# RF_Module.net
KiCad netlist of a schematic drawn in Altium Designer
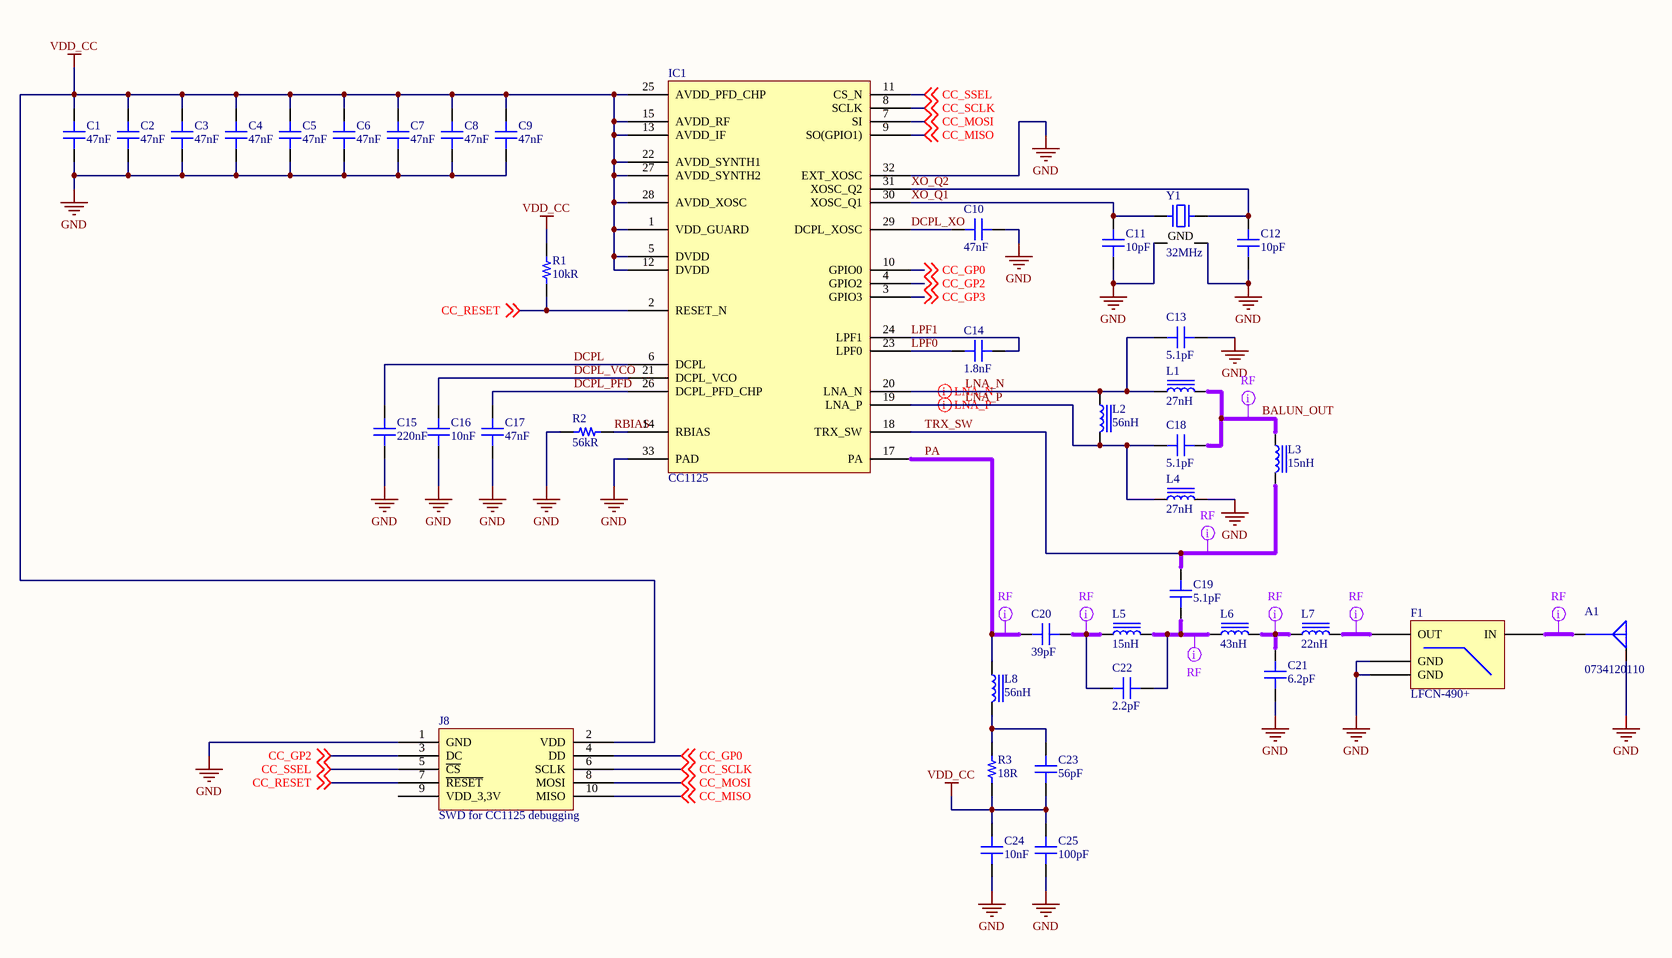
[diagram p0: RF Module.SchDoc]

(export (version "E")
  (design (tool "Eeschema 10.0.6"))
  (components
    (comp (ref "A1")
      (value "0734120110")
      (footprint "MOLEX SD-734120110")
      (description "Conn Micro Coaxial RCP 0Hz to 6GHz 50Ohm Solder ST SMD Gold Embossed T/R")
      (libsource (lib "SCH - RF - ANTENNA - BASIC ANTENNA") (part "Basic Antenna"))
    )
    (comp (ref "C1")
      (value "47nF")
      (footprint "CAP 0402/1005")
      (description "CAP CER 0.047UF 10V X7R 0402")
      (fields (field (name "TOLERANCE") "10%") (field (name "VOLTAGE") "16V"))
      (libsource (lib "SCH - PASSIVES - CAPACITOR") (part "Capacitor"))
    )
    (comp (ref "C2")
      (value "47nF")
      (footprint "CAP 0402/1005")
      (description "CAP CER 0.047UF 10V X7R 0402")
      (fields (field (name "TOLERANCE") "10%") (field (name "VOLTAGE") "16V"))
      (libsource (lib "SCH - PASSIVES - CAPACITOR") (part "Capacitor"))
    )
    (comp (ref "C3")
      (value "47nF")
      (footprint "CAP 0402/1005")
      (description "CAP CER 0.047UF 10V X7R 0402")
      (fields (field (name "TOLERANCE") "10%") (field (name "VOLTAGE") "16V"))
      (libsource (lib "SCH - PASSIVES - CAPACITOR") (part "Capacitor"))
    )
    (comp (ref "C4")
      (value "47nF")
      (footprint "CAP 0402/1005")
      (description "CAP CER 0.047UF 10V X7R 0402")
      (fields (field (name "TOLERANCE") "10%") (field (name "VOLTAGE") "16V"))
      (libsource (lib "SCH - PASSIVES - CAPACITOR") (part "Capacitor"))
    )
    (comp (ref "C5")
      (value "47nF")
      (footprint "CAP 0402/1005")
      (description "CAP CER 0.047UF 10V X7R 0402")
      (fields (field (name "TOLERANCE") "10%") (field (name "VOLTAGE") "16V"))
      (libsource (lib "SCH - PASSIVES - CAPACITOR") (part "Capacitor"))
    )
    (comp (ref "C6")
      (value "47nF")
      (footprint "CAP 0402/1005")
      (description "CAP CER 0.047UF 10V X7R 0402")
      (fields (field (name "TOLERANCE") "10%") (field (name "VOLTAGE") "16V"))
      (libsource (lib "SCH - PASSIVES - CAPACITOR") (part "Capacitor"))
    )
    (comp (ref "C7")
      (value "47nF")
      (footprint "CAP 0402/1005")
      (description "CAP CER 0.047UF 10V X7R 0402")
      (fields (field (name "TOLERANCE") "10%") (field (name "VOLTAGE") "16V"))
      (libsource (lib "SCH - PASSIVES - CAPACITOR") (part "Capacitor"))
    )
    (comp (ref "C8")
      (value "47nF")
      (footprint "CAP 0402/1005")
      (description "CAP CER 0.047UF 10V X7R 0402")
      (fields (field (name "TOLERANCE") "10%") (field (name "VOLTAGE") "16V"))
      (libsource (lib "SCH - PASSIVES - CAPACITOR") (part "Capacitor"))
    )
    (comp (ref "C9")
      (value "47nF")
      (footprint "CAP 0402/1005")
      (description "CAP CER 0.047UF 10V X7R 0402")
      (fields (field (name "TOLERANCE") "10%") (field (name "VOLTAGE") "16V"))
      (libsource (lib "SCH - PASSIVES - CAPACITOR") (part "Capacitor"))
    )
    (comp (ref "C10")
      (value "47nF")
      (footprint "CAP 0402/1005")
      (description "CAP CER 0.047UF 10V X7R 0402")
      (fields (field (name "TOLERANCE") "10%") (field (name "VOLTAGE") "16V"))
      (libsource (lib "SCH - PASSIVES - CAPACITOR") (part "Capacitor"))
    )
    (comp (ref "C11")
      (value "10pF")
      (footprint "CAP 0402/1005")
      (description "CAP CER 10PF 50V C0G/NPO 0402")
      (fields (field (name "TOLERANCE") "5%") (field (name "VOLTAGE") "50V"))
      (libsource (lib "SCH - PASSIVES - CAPACITOR") (part "Capacitor"))
    )
    (comp (ref "C12")
      (value "10pF")
      (footprint "CAP 0402/1005")
      (description "CAP CER 10PF 50V C0G/NPO 0402")
      (fields (field (name "TOLERANCE") "5%") (field (name "VOLTAGE") "50V"))
      (libsource (lib "SCH - PASSIVES - CAPACITOR") (part "Capacitor"))
    )
    (comp (ref "C13")
      (value "5.1pF")
      (footprint "CAP 0402/1005 RF")
      (description "CAP CER 5.1PF 50V C0G/NP0 0402")
      (fields (field (name "VOLTAGE") "50V"))
      (libsource (lib "SCH - PASSIVES - CAPACITOR") (part "Capacitor"))
    )
    (comp (ref "C14")
      (value "1.8nF")
      (footprint "CAP 0402/1005")
      (description "CAP CER 1800PF 50V X7R 0402")
      (fields (field (name "TOLERANCE") "10%"))
      (libsource (lib "SCH - PASSIVES - CAPACITOR") (part "Capacitor"))
    )
    (comp (ref "C15")
      (value "220nF")
      (footprint "CAP 0402/1005")
      (description "Cap Ceramic 0.22uF 10V X7R 10% SMD 0402 125C Paper T/R")
      (fields (field (name "TOLERANCE") "10%"))
      (libsource (lib "SCH - PASSIVES - CAPACITOR") (part "Capacitor"))
    )
    (comp (ref "C16")
      (value "10nF")
      (footprint "CAP 0402/1005")
      (description "TAIYO YUDEN - TMK105B7103KV-F - CERAMIC CAPACITOR 0.01UF, 25V, X7R, 10%, 0402, FULL REEL")
      (fields (field (name "TOLERANCE") "10%") (field (name "VOLTAGE") "25V"))
      (libsource (lib "SCH - PASSIVES - CAPACITOR") (part "Capacitor"))
    )
    (comp (ref "C17")
      (value "47nF")
      (footprint "CAP 0402/1005")
      (description "CAP CER 0.047UF 10V X7R 0402")
      (fields (field (name "TOLERANCE") "10%") (field (name "VOLTAGE") "16V"))
      (libsource (lib "SCH - PASSIVES - CAPACITOR") (part "Capacitor"))
    )
    (comp (ref "C18")
      (value "5.1pF")
      (footprint "CAP 0402/1005 RF")
      (description "CAP CER 5.1PF 50V C0G/NP0 0402")
      (fields (field (name "VOLTAGE") "50V"))
      (libsource (lib "SCH - PASSIVES - CAPACITOR") (part "Capacitor"))
    )
    (comp (ref "C19")
      (value "5.1pF")
      (footprint "CAP 0402/1005 RF")
      (description "CAP CER 5.1PF 50V C0G/NP0 0402")
      (fields (field (name "VOLTAGE") "50V"))
      (libsource (lib "SCH - PASSIVES - CAPACITOR") (part "Capacitor"))
    )
    (comp (ref "C20")
      (value "39pF")
      (footprint "CAP 0402/1005 RF")
      (fields (field (name "TOLERANCE") "5%"))
      (libsource (lib "SCH - PASSIVES - CAPACITOR") (part "Capacitor"))
    )
    (comp (ref "C21")
      (value "6.2pF")
      (footprint "CAP 0402/1005 RF")
      (libsource (lib "SCH - PASSIVES - CAPACITOR") (part "Capacitor"))
    )
    (comp (ref "C22")
      (value "2.2pF")
      (footprint "CAP 0402/1005 RF")
      (fields (field (name "VOLTAGE") "50V"))
      (libsource (lib "SCH - PASSIVES - CAPACITOR") (part "Capacitor"))
    )
    (comp (ref "C23")
      (value "56pF")
      (footprint "CAP 0402/1005 RF")
      (description "Cap Ceramic 56pF 50V C0G 1% SMD 0402 125°C Paper T/R")
      (fields (field (name "TOLERANCE") "1%"))
      (libsource (lib "SCH - PASSIVES - CAPACITOR") (part "Capacitor"))
    )
    (comp (ref "C24")
      (value "10nF")
      (footprint "CAP 0402/1005 RF")
      (description "Cap Ceramic 0.01uF 16V X7R 5% SMD 0402 125C Paper T/R")
      (fields (field (name "TOLERANCE") "5%"))
      (libsource (lib "SCH - PASSIVES - CAPACITOR") (part "Capacitor"))
    )
    (comp (ref "C25")
      (value "100pF")
      (footprint "CAP 0402/1005 RF")
      (description "CAP CER SMD CBR 0402 100PF 5% 25")
      (fields (field (name "TOLERANCE") "5%"))
      (libsource (lib "SCH - PASSIVES - CAPACITOR") (part "Capacitor"))
    )
    (comp (ref "F1")
      (value "LFCN-490+")
      (footprint "PCB - RF FILTER - MINICIRCUITS FV1206")
      (description "490MHz Low Pass Filter")
      (libsource (lib "SCH - RF - FILTER - MINICIRCUITS LFCN-490") (part "SCH - RF - FILTER - MINICIRCUITS LFCN-490"))
    )
    (comp (ref "IC1")
      (value "CC1125")
      (footprint "PCB - LEADLESS - QFN - TI PVQFN-32 5X5MM RHB")
      (description "RF Transceiver Ultra-Hi Perf RF Narrowbd Transceiver")
      (libsource (lib "SCH - RF - IC - TI CC1120") (part "SCH - RF - IC - TI CC1120"))
    )
    (comp (ref "J8")
      (value "SWD for CC1125 debugging")
      (footprint "10 Pin SWD")
      (libsource (lib "CC1125_Sub1GHzTransceiver") (part "SWD_CC"))
    )
    (comp (ref "L1")
      (value "27nH")
      (footprint "IND 0402/1005 RF WW")
      (fields (field (name "TOLERANCE") "2%"))
      (libsource (lib "SCH - PASSIVES - INDUCTOR") (part "Inductor"))
    )
    (comp (ref "L2")
      (value "56nH")
      (footprint "IND 0402/1005 RF WW")
      (description "Fixed Inductors 56nH 2%")
      (fields (field (name "TOLERANCE") "2%"))
      (libsource (lib "SCH - PASSIVES - INDUCTOR") (part "Inductor"))
    )
    (comp (ref "L3")
      (value "15nH")
      (footprint "IND 0402/1005 RF WW")
      (description "FIXED IND 15NH 1.15A 114 MOHM")
      (fields (field (name "TOLERANCE") "2%"))
      (libsource (lib "SCH - PASSIVES - INDUCTOR") (part "Inductor"))
    )
    (comp (ref "L4")
      (value "27nH")
      (footprint "IND 0402/1005 RF WW")
      (fields (field (name "TOLERANCE") "2%"))
      (libsource (lib "SCH - PASSIVES - INDUCTOR") (part "Inductor"))
    )
    (comp (ref "L5")
      (value "15nH")
      (footprint "IND 0402/1005 RF WW")
      (description "FIXED IND 15NH 1.15A 114 MOHM")
      (fields (field (name "TOLERANCE") "2%"))
      (libsource (lib "SCH - PASSIVES - INDUCTOR") (part "Inductor"))
    )
    (comp (ref "L6")
      (value "43nH")
      (footprint "IND 0402/1005 RF WW")
      (description "Fixed Inductors 43nH 2% 100MHz")
      (fields (field (name "TOLERANCE") "2%"))
      (libsource (lib "SCH - PASSIVES - INDUCTOR") (part "Inductor"))
    )
    (comp (ref "L7")
      (value "22nH")
      (footprint "IND 0402/1005 RF WW")
      (description "FIXED IND 22NH 780MA 202 MOHM")
      (fields (field (name "TOLERANCE") "2%"))
      (libsource (lib "SCH - PASSIVES - INDUCTOR") (part "Inductor"))
    )
    (comp (ref "L8")
      (value "56nH")
      (footprint "IND 0402/1005 RF WW")
      (description "Fixed Inductors 56nH 2%")
      (fields (field (name "TOLERANCE") "2%"))
      (libsource (lib "SCH - PASSIVES - INDUCTOR") (part "Inductor"))
    )
    (comp (ref "R1")
      (value "10kR")
      (footprint "RES 0402/1005")
      (description "RES SMD 10K OHM 5% 1/16W 0402")
      (fields (field (name "TOLERANCE") "5%"))
      (libsource (lib "SCH - PASSIVES - RESISTOR") (part "Resistor"))
    )
    (comp (ref "R2")
      (value "56kR")
      (footprint "RES 0402/1005")
      (description "RES SMD 56K OHM 5% 1/16W 0402")
      (fields (field (name "TOLERANCE") "5%"))
      (libsource (lib "SCH - PASSIVES - RESISTOR") (part "Resistor"))
    )
    (comp (ref "R3")
      (value "18R")
      (footprint "RES 0402/1005")
      (fields (field (name "TOLERANCE") "1%"))
      (libsource (lib "SCH - PASSIVES - RESISTOR") (part "Resistor"))
    )
    (comp (ref "Y1")
      (value "32MHz")
      (footprint "ABRACON ABM8G")
      (description "CRYSTAL 32.0000MHZ 10PF SMD")
      (fields (field (name "TOLERANCE") "30ppm"))
      (libsource (lib "SCH - CRYSTALS - ABRACON CRYSTAL ABM8G") (part "Abracon Crystal ABM8G"))
    )
  )
  (nets
    (net (code "1") (name "/BALUN_OUT") (class "Default")
      (node (ref "C18") (pin "2") (pinfunction "2_2") (pintype "passive"))
      (node (ref "L1") (pin "2") (pinfunction "2_2") (pintype "passive"))
      (node (ref "L3") (pin "1") (pinfunction "1_1") (pintype "passive"))
    )
    (net (code "2") (name "/DCPL") (class "Default")
      (node (ref "C15") (pin "2") (pinfunction "2_2") (pintype "passive"))
      (node (ref "IC1") (pin "6") (pinfunction "DCPL_6") (pintype "passive"))
    )
    (net (code "3") (name "/DCPL_PFD") (class "Default")
      (node (ref "C17") (pin "2") (pinfunction "2_2") (pintype "passive"))
      (node (ref "IC1") (pin "26") (pinfunction "DCPL_PFD_CHP_26") (pintype "passive"))
    )
    (net (code "4") (name "/DCPL_VCO") (class "Default")
      (node (ref "C16") (pin "2") (pinfunction "2_2") (pintype "passive"))
      (node (ref "IC1") (pin "21") (pinfunction "DCPL_VCO_21") (pintype "passive"))
    )
    (net (code "5") (name "/DCPL_XO") (class "Default")
      (node (ref "C10") (pin "2") (pinfunction "2_2") (pintype "passive"))
      (node (ref "IC1") (pin "29") (pinfunction "DCPL_XOSC_29") (pintype "passive"))
    )
    (net (code "6") (name "/LNA_N") (class "Default")
      (node (ref "C13") (pin "1") (pinfunction "1_1") (pintype "passive"))
      (node (ref "IC1") (pin "20") (pinfunction "LNA_N_20") (pintype "passive"))
      (node (ref "L1") (pin "1") (pinfunction "1_1") (pintype "passive"))
      (node (ref "L2") (pin "1") (pinfunction "1_1") (pintype "passive"))
    )
    (net (code "7") (name "/LNA_P") (class "Default")
      (node (ref "C18") (pin "1") (pinfunction "1_1") (pintype "passive"))
      (node (ref "IC1") (pin "19") (pinfunction "LNA_P_19") (pintype "passive"))
      (node (ref "L2") (pin "2") (pinfunction "2_2") (pintype "passive"))
      (node (ref "L4") (pin "1") (pinfunction "1_1") (pintype "passive"))
    )
    (net (code "8") (name "/LPF0") (class "Default")
      (node (ref "C14") (pin "2") (pinfunction "2_2") (pintype "passive"))
      (node (ref "IC1") (pin "23") (pinfunction "LPF0_23") (pintype "passive"))
    )
    (net (code "9") (name "/LPF1") (class "Default")
      (node (ref "C14") (pin "1") (pinfunction "1_1") (pintype "passive"))
      (node (ref "IC1") (pin "24") (pinfunction "LPF1_24") (pintype "passive"))
    )
    (net (code "10") (name "/PA") (class "Default")
      (node (ref "C20") (pin "1") (pinfunction "1_1") (pintype "passive"))
      (node (ref "IC1") (pin "17") (pinfunction "PA_17") (pintype "passive"))
      (node (ref "L8") (pin "1") (pinfunction "1_1") (pintype "passive"))
    )
    (net (code "11") (name "/RBIAS") (class "Default")
      (node (ref "IC1") (pin "14") (pinfunction "RBIAS_14") (pintype "passive"))
      (node (ref "R2") (pin "1") (pinfunction "1_1") (pintype "passive"))
    )
    (net (code "12") (name "/TRX_SW") (class "Default")
      (node (ref "C19") (pin "2") (pinfunction "2_2") (pintype "passive"))
      (node (ref "IC1") (pin "18") (pinfunction "TRX_SW_18") (pintype "passive"))
      (node (ref "L3") (pin "2") (pinfunction "2_2") (pintype "passive"))
    )
    (net (code "13") (name "/XO_Q1") (class "Default")
      (node (ref "C11") (pin "2") (pinfunction "2_2") (pintype "passive"))
      (node (ref "IC1") (pin "30") (pinfunction "XOSC_Q1_30") (pintype "passive"))
      (node (ref "Y1") (pin "1") (pinfunction "1_1") (pintype "passive"))
    )
    (net (code "14") (name "/XO_Q2") (class "Default")
      (node (ref "C12") (pin "2") (pinfunction "2_2") (pintype "passive"))
      (node (ref "IC1") (pin "31") (pinfunction "XOSC_Q2_31") (pintype "passive"))
      (node (ref "Y1") (pin "3") (pinfunction "3_3") (pintype "passive"))
    )
    (net (code "15") (name "CC_GP0") (class "Default")
      (node (ref "IC1") (pin "10") (pinfunction "GPIO0_10") (pintype "passive"))
      (node (ref "J8") (pin "4") (pinfunction "DD_4") (pintype "passive"))
    )
    (net (code "16") (name "CC_GP2") (class "Default")
      (node (ref "IC1") (pin "4") (pinfunction "GPIO2_4") (pintype "passive"))
      (node (ref "J8") (pin "3") (pinfunction "DC_3") (pintype "passive"))
    )
    (net (code "17") (name "CC_GP3") (class "Default")
      (node (ref "IC1") (pin "3") (pinfunction "GPIO3_3") (pintype "passive"))
    )
    (net (code "18") (name "CC_MISO") (class "Default")
      (node (ref "IC1") (pin "9") (pinfunction "SO(GPIO1)_9") (pintype "passive"))
      (node (ref "J8") (pin "10") (pinfunction "MISO_10") (pintype "passive"))
    )
    (net (code "19") (name "CC_MOSI") (class "Default")
      (node (ref "IC1") (pin "7") (pinfunction "SI_7") (pintype "passive"))
      (node (ref "J8") (pin "8") (pinfunction "MOSI_8") (pintype "passive"))
    )
    (net (code "20") (name "CC_RESET") (class "Default")
      (node (ref "IC1") (pin "2") (pinfunction "RESET_N_2") (pintype "passive"))
      (node (ref "J8") (pin "7") (pinfunction "~{RESET}_7") (pintype "passive"))
      (node (ref "R1") (pin "1") (pinfunction "1_1") (pintype "passive"))
    )
    (net (code "21") (name "CC_SCLK") (class "Default")
      (node (ref "IC1") (pin "8") (pinfunction "SCLK_8") (pintype "passive"))
      (node (ref "J8") (pin "6") (pinfunction "SCLK_6") (pintype "passive"))
    )
    (net (code "22") (name "CC_SSEL") (class "Default")
      (node (ref "IC1") (pin "11") (pinfunction "CS_N_11") (pintype "passive"))
      (node (ref "J8") (pin "5") (pinfunction "~{CS}_5") (pintype "passive"))
    )
    (net (code "23") (name "GND") (class "Default")
      (node (ref "A1") (pin "G") (pinfunction "G_G") (pintype "passive"))
      (node (ref "C1") (pin "1") (pinfunction "1_1") (pintype "passive"))
      (node (ref "C10") (pin "1") (pinfunction "1_1") (pintype "passive"))
      (node (ref "C11") (pin "1") (pinfunction "1_1") (pintype "passive"))
      (node (ref "C12") (pin "1") (pinfunction "1_1") (pintype "passive"))
      (node (ref "C13") (pin "2") (pinfunction "2_2") (pintype "passive"))
      (node (ref "C15") (pin "1") (pinfunction "1_1") (pintype "passive"))
      (node (ref "C16") (pin "1") (pinfunction "1_1") (pintype "passive"))
      (node (ref "C17") (pin "1") (pinfunction "1_1") (pintype "passive"))
      (node (ref "C2") (pin "1") (pinfunction "1_1") (pintype "passive"))
      (node (ref "C21") (pin "1") (pinfunction "1_1") (pintype "passive"))
      (node (ref "C24") (pin "1") (pinfunction "1_1") (pintype "passive"))
      (node (ref "C25") (pin "1") (pinfunction "1_1") (pintype "passive"))
      (node (ref "C3") (pin "1") (pinfunction "1_1") (pintype "passive"))
      (node (ref "C4") (pin "1") (pinfunction "1_1") (pintype "passive"))
      (node (ref "C5") (pin "1") (pinfunction "1_1") (pintype "passive"))
      (node (ref "C6") (pin "1") (pinfunction "1_1") (pintype "passive"))
      (node (ref "C7") (pin "1") (pinfunction "1_1") (pintype "passive"))
      (node (ref "C8") (pin "1") (pinfunction "1_1") (pintype "passive"))
      (node (ref "C9") (pin "1") (pinfunction "1_1") (pintype "passive"))
      (node (ref "F1") (pin "2") (pinfunction "GND_2") (pintype "passive"))
      (node (ref "F1") (pin "4") (pinfunction "GND_4") (pintype "passive"))
      (node (ref "IC1") (pin "32") (pinfunction "EXT_XOSC_32") (pintype "passive"))
      (node (ref "IC1") (pin "33") (pinfunction "PAD_33") (pintype "passive"))
      (node (ref "J8") (pin "1") (pinfunction "GND_1") (pintype "passive"))
      (node (ref "L4") (pin "2") (pinfunction "2_2") (pintype "passive"))
      (node (ref "R2") (pin "2") (pinfunction "2_2") (pintype "passive"))
      (node (ref "Y1") (pin "2") (pinfunction "GND_2") (pintype "passive"))
      (node (ref "Y1") (pin "4") (pinfunction "GND_4") (pintype "passive"))
    )
    (net (code "24") (name "Net-(C19-Pad1)") (class "Default")
      (node (ref "C19") (pin "1") (pinfunction "1_1") (pintype "passive"))
      (node (ref "C22") (pin "1") (pinfunction "1_1") (pintype "passive"))
      (node (ref "L5") (pin "2") (pinfunction "2_2") (pintype "passive"))
      (node (ref "L6") (pin "1") (pinfunction "1_1") (pintype "passive"))
    )
    (net (code "25") (name "Net-(C20-Pad2)") (class "Default")
      (node (ref "C20") (pin "2") (pinfunction "2_2") (pintype "passive"))
      (node (ref "C22") (pin "2") (pinfunction "2_2") (pintype "passive"))
      (node (ref "L5") (pin "1") (pinfunction "1_1") (pintype "passive"))
    )
    (net (code "26") (name "Net-(C21-Pad2)") (class "Default")
      (node (ref "C21") (pin "2") (pinfunction "2_2") (pintype "passive"))
      (node (ref "L6") (pin "2") (pinfunction "2_2") (pintype "passive"))
      (node (ref "L7") (pin "1") (pinfunction "1_1") (pintype "passive"))
    )
    (net (code "27") (name "Net-(C23-Pad2)") (class "Default")
      (node (ref "C23") (pin "2") (pinfunction "2_2") (pintype "passive"))
      (node (ref "L8") (pin "2") (pinfunction "2_2") (pintype "passive"))
      (node (ref "R3") (pin "2") (pinfunction "2_2") (pintype "passive"))
    )
    (net (code "28") (name "Net-(F1-IN)") (class "Default")
      (node (ref "A1") (pin "S") (pinfunction "S_S") (pintype "passive"))
      (node (ref "F1") (pin "1") (pinfunction "IN_1") (pintype "passive"))
    )
    (net (code "29") (name "Net-(F1-OUT)") (class "Default")
      (node (ref "F1") (pin "3") (pinfunction "OUT_3") (pintype "passive"))
      (node (ref "L7") (pin "2") (pinfunction "2_2") (pintype "passive"))
    )
    (net (code "30") (name "VDD_CC") (class "Default")
      (node (ref "C1") (pin "2") (pinfunction "2_2") (pintype "passive"))
      (node (ref "C2") (pin "2") (pinfunction "2_2") (pintype "passive"))
      (node (ref "C23") (pin "1") (pinfunction "1_1") (pintype "passive"))
      (node (ref "C24") (pin "2") (pinfunction "2_2") (pintype "passive"))
      (node (ref "C25") (pin "2") (pinfunction "2_2") (pintype "passive"))
      (node (ref "C3") (pin "2") (pinfunction "2_2") (pintype "passive"))
      (node (ref "C4") (pin "2") (pinfunction "2_2") (pintype "passive"))
      (node (ref "C5") (pin "2") (pinfunction "2_2") (pintype "passive"))
      (node (ref "C6") (pin "2") (pinfunction "2_2") (pintype "passive"))
      (node (ref "C7") (pin "2") (pinfunction "2_2") (pintype "passive"))
      (node (ref "C8") (pin "2") (pinfunction "2_2") (pintype "passive"))
      (node (ref "C9") (pin "2") (pinfunction "2_2") (pintype "passive"))
      (node (ref "IC1") (pin "1") (pinfunction "VDD_GUARD_1") (pintype "passive"))
      (node (ref "IC1") (pin "12") (pinfunction "DVDD_12") (pintype "passive"))
      (node (ref "IC1") (pin "13") (pinfunction "AVDD_IF_13") (pintype "passive"))
      (node (ref "IC1") (pin "15") (pinfunction "AVDD_RF_15") (pintype "passive"))
      (node (ref "IC1") (pin "22") (pinfunction "AVDD_SYNTH1_22") (pintype "passive"))
      (node (ref "IC1") (pin "25") (pinfunction "AVDD_PFD_CHP_25") (pintype "passive"))
      (node (ref "IC1") (pin "27") (pinfunction "AVDD_SYNTH2_27") (pintype "passive"))
      (node (ref "IC1") (pin "28") (pinfunction "AVDD_XOSC_28") (pintype "passive"))
      (node (ref "IC1") (pin "5") (pinfunction "DVDD_5") (pintype "passive"))
      (node (ref "J8") (pin "2") (pinfunction "VDD_2") (pintype "passive"))
      (node (ref "R1") (pin "2") (pinfunction "2_2") (pintype "passive"))
      (node (ref "R3") (pin "1") (pinfunction "1_1") (pintype "passive"))
    )
    (net (code "31") (name "unconnected-(J8-VDD_3,3V-Pad9)") (class "Default")
      (node (ref "J8") (pin "9") (pinfunction "VDD_3,3V_9") (pintype "passive"))
    )
  )
)
